# vcf20.net
KiCad netlist of a schematic drawn in EAGLE
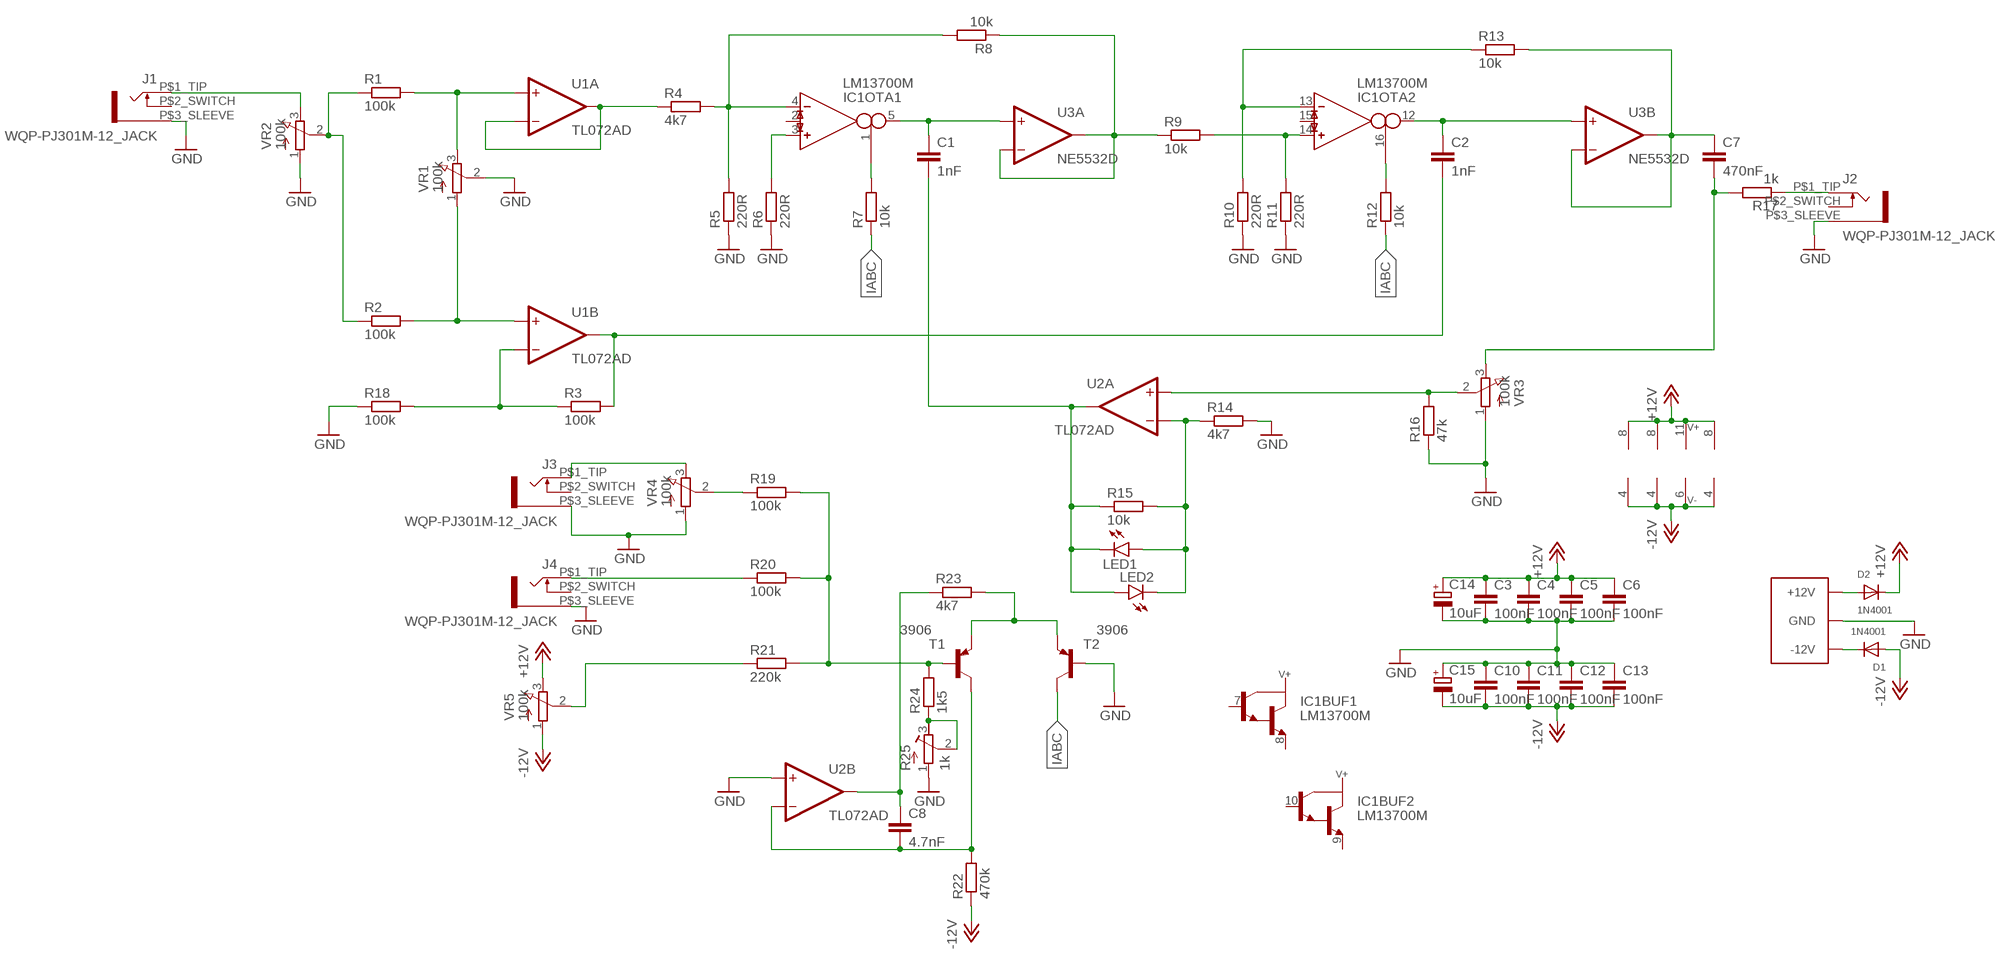
[diagram p0: schematic, sheet 1]

(export (version "E")
  (design (tool "Eeschema 10.0.6"))
  (components
    (comp (ref "C1")
      (value "1nF")
      (footprint "eagle-import:C0402")
      (libsource (lib "eagle-import") (part "C-EUC0402"))
    )
    (comp (ref "C2")
      (value "1nF")
      (footprint "eagle-import:C0402")
      (libsource (lib "eagle-import") (part "C-EUC0402"))
    )
    (comp (ref "C3")
      (value "100nF")
      (footprint "eagle-import:C0402")
      (libsource (lib "eagle-import") (part "C-EUC0402"))
    )
    (comp (ref "C4")
      (value "100nF")
      (footprint "eagle-import:C0402")
      (libsource (lib "eagle-import") (part "C-EUC0402"))
    )
    (comp (ref "C5")
      (value "100nF")
      (footprint "eagle-import:C0402")
      (libsource (lib "eagle-import") (part "C-EUC0402"))
    )
    (comp (ref "C6")
      (value "100nF")
      (footprint "eagle-import:C0402")
      (libsource (lib "eagle-import") (part "C-EUC0402"))
    )
    (comp (ref "C7")
      (value "470nF")
      (footprint "eagle-import:C0402")
      (libsource (lib "eagle-import") (part "C-EUC0402"))
    )
    (comp (ref "C8")
      (value "4.7nF")
      (footprint "eagle-import:C0402")
      (libsource (lib "eagle-import") (part "C-EUC0402"))
    )
    (comp (ref "C9")
      (value "EURO_POWER_LOCKFAT-LOCK")
      (footprint "eagle-import:EURO_PWR_HEADER_LOCK")
      (libsource (lib "eagle-import") (part "EURO_POWER_LOCKFAT-LOCK"))
    )
    (comp (ref "C10")
      (value "100nF")
      (footprint "eagle-import:C0402")
      (libsource (lib "eagle-import") (part "C-EUC0402"))
    )
    (comp (ref "C11")
      (value "100nF")
      (footprint "eagle-import:C0402")
      (libsource (lib "eagle-import") (part "C-EUC0402"))
    )
    (comp (ref "C12")
      (value "100nF")
      (footprint "eagle-import:C0402")
      (libsource (lib "eagle-import") (part "C-EUC0402"))
    )
    (comp (ref "C13")
      (value "100nF")
      (footprint "eagle-import:C0402")
      (libsource (lib "eagle-import") (part "C-EUC0402"))
    )
    (comp (ref "C14")
      (value "10uF")
      (footprint "eagle-import:PANASONIC_C")
      (libsource (lib "eagle-import") (part "CPOL-EUC"))
    )
    (comp (ref "C15")
      (value "10uF")
      (footprint "eagle-import:PANASONIC_C")
      (libsource (lib "eagle-import") (part "CPOL-EUC"))
    )
    (comp (ref "D1")
      (value "1N4001")
      (footprint "eagle-import:SMADIODE")
      (libsource (lib "eagle-import") (part "DIODESMA"))
    )
    (comp (ref "D2")
      (value "1N4001")
      (footprint "eagle-import:SMADIODE")
      (libsource (lib "eagle-import") (part "DIODESMA"))
    )
    (comp (ref "IC1")
      (value "LM13700M")
      (footprint "eagle-import:SO16")
      (libsource (lib "eagle-import") (part "LM13700M"))
    )
    (comp (ref "J1")
      (value "WQP-PJ301M-12_JACK")
      (footprint "eagle-import:WQP-PJ301M-12_JACK")
      (libsource (lib "eagle-import") (part "WQP-PJ301M-12_JACK"))
    )
    (comp (ref "J2")
      (value "WQP-PJ301M-12_JACK")
      (footprint "eagle-import:WQP-PJ301M-12_JACK")
      (libsource (lib "eagle-import") (part "WQP-PJ301M-12_JACK"))
    )
    (comp (ref "J3")
      (value "WQP-PJ301M-12_JACK")
      (footprint "eagle-import:WQP-PJ301M-12_JACK")
      (libsource (lib "eagle-import") (part "WQP-PJ301M-12_JACK"))
    )
    (comp (ref "J4")
      (value "WQP-PJ301M-12_JACK")
      (footprint "eagle-import:WQP-PJ301M-12_JACK")
      (libsource (lib "eagle-import") (part "WQP-PJ301M-12_JACK"))
    )
    (comp (ref "LED1")
      (value "LEDSML0603")
      (footprint "eagle-import:SML0603")
      (libsource (lib "eagle-import") (part "LEDSML0603"))
    )
    (comp (ref "LED2")
      (value "LEDSML0603")
      (footprint "eagle-import:SML0603")
      (libsource (lib "eagle-import") (part "LEDSML0603"))
    )
    (comp (ref "R1")
      (value "100k")
      (footprint "eagle-import:R0402")
      (libsource (lib "eagle-import") (part "R-EU_R0402"))
    )
    (comp (ref "R2")
      (value "100k")
      (footprint "eagle-import:R0402")
      (libsource (lib "eagle-import") (part "R-EU_R0402"))
    )
    (comp (ref "R3")
      (value "100k")
      (footprint "eagle-import:R0402")
      (libsource (lib "eagle-import") (part "R-EU_R0402"))
    )
    (comp (ref "R4")
      (value "4k7")
      (footprint "eagle-import:R0402")
      (libsource (lib "eagle-import") (part "R-EU_R0402"))
    )
    (comp (ref "R5")
      (value "220R")
      (footprint "eagle-import:R0402")
      (libsource (lib "eagle-import") (part "R-EU_R0402"))
    )
    (comp (ref "R6")
      (value "220R")
      (footprint "eagle-import:R0402")
      (libsource (lib "eagle-import") (part "R-EU_R0402"))
    )
    (comp (ref "R7")
      (value "10k")
      (footprint "eagle-import:R0402")
      (libsource (lib "eagle-import") (part "R-EU_R0402"))
    )
    (comp (ref "R8")
      (value "10k")
      (footprint "eagle-import:R0402")
      (libsource (lib "eagle-import") (part "R-EU_R0402"))
    )
    (comp (ref "R9")
      (value "10k")
      (footprint "eagle-import:R0402")
      (libsource (lib "eagle-import") (part "R-EU_R0402"))
    )
    (comp (ref "R10")
      (value "220R")
      (footprint "eagle-import:R0402")
      (libsource (lib "eagle-import") (part "R-EU_R0402"))
    )
    (comp (ref "R11")
      (value "220R")
      (footprint "eagle-import:R0402")
      (libsource (lib "eagle-import") (part "R-EU_R0402"))
    )
    (comp (ref "R12")
      (value "10k")
      (footprint "eagle-import:R0402")
      (libsource (lib "eagle-import") (part "R-EU_R0402"))
    )
    (comp (ref "R13")
      (value "10k")
      (footprint "eagle-import:R0402")
      (libsource (lib "eagle-import") (part "R-EU_R0402"))
    )
    (comp (ref "R14")
      (value "4k7")
      (footprint "eagle-import:R0402")
      (libsource (lib "eagle-import") (part "R-EU_R0402"))
    )
    (comp (ref "R15")
      (value "10k")
      (footprint "eagle-import:R0402")
      (libsource (lib "eagle-import") (part "R-EU_R0402"))
    )
    (comp (ref "R16")
      (value "47k")
      (footprint "eagle-import:R0402")
      (libsource (lib "eagle-import") (part "R-EU_R0402"))
    )
    (comp (ref "R17")
      (value "1k")
      (footprint "eagle-import:R0402")
      (libsource (lib "eagle-import") (part "R-EU_R0402"))
    )
    (comp (ref "R18")
      (value "100k")
      (footprint "eagle-import:R0402")
      (libsource (lib "eagle-import") (part "R-EU_R0402"))
    )
    (comp (ref "R19")
      (value "100k")
      (footprint "eagle-import:R0402")
      (libsource (lib "eagle-import") (part "R-EU_R0402"))
    )
    (comp (ref "R20")
      (value "100k")
      (footprint "eagle-import:R0402")
      (libsource (lib "eagle-import") (part "R-EU_R0402"))
    )
    (comp (ref "R21")
      (value "220k")
      (footprint "eagle-import:R0402")
      (libsource (lib "eagle-import") (part "R-EU_R0402"))
    )
    (comp (ref "R22")
      (value "470k")
      (footprint "eagle-import:R0402")
      (libsource (lib "eagle-import") (part "R-EU_R0402"))
    )
    (comp (ref "R23")
      (value "4k7")
      (footprint "eagle-import:R0402")
      (libsource (lib "eagle-import") (part "R-EU_R0402"))
    )
    (comp (ref "R24")
      (value "1k5")
      (footprint "eagle-import:R0402")
      (libsource (lib "eagle-import") (part "R-EU_R0402"))
    )
    (comp (ref "R25")
      (value "1k")
      (footprint "eagle-import:RTRIM64W")
      (libsource (lib "eagle-import") (part "R-TRIMM64W"))
    )
    (comp (ref "T1")
      (value "3906")
      (footprint "eagle-import:SOT23-BEC")
      (libsource (lib "eagle-import") (part "-PNP-SOT23-BECMMBT3906LT1"))
    )
    (comp (ref "T2")
      (value "3906")
      (footprint "eagle-import:SOT23-BEC")
      (libsource (lib "eagle-import") (part "-PNP-SOT23-BECMMBT3906LT1"))
    )
    (comp (ref "U1")
      (value "TL072AD")
      (footprint "eagle-import:SOIC8")
      (libsource (lib "eagle-import") (part "TL072DA"))
    )
    (comp (ref "U2")
      (value "TL072AD")
      (footprint "eagle-import:SOIC8")
      (libsource (lib "eagle-import") (part "TL072DA"))
    )
    (comp (ref "U3")
      (value "NE5532D")
      (footprint "eagle-import:SOIC8")
      (libsource (lib "eagle-import") (part "NE5532D"))
    )
    (comp (ref "VR1")
      (value "100k")
      (footprint "eagle-import:9MM_SNAP-IN_POT")
      (libsource (lib "eagle-import") (part "9MM_SNAP-IN_POT_"))
    )
    (comp (ref "VR2")
      (value "100k")
      (footprint "eagle-import:9MM_SNAP-IN_POT")
      (libsource (lib "eagle-import") (part "9MM_SNAP-IN_POT_"))
    )
    (comp (ref "VR3")
      (value "100k")
      (footprint "eagle-import:9MM_SNAP-IN_POT")
      (libsource (lib "eagle-import") (part "9MM_SNAP-IN_POT_"))
    )
    (comp (ref "VR4")
      (value "100k")
      (footprint "eagle-import:9MM_SNAP-IN_POT")
      (libsource (lib "eagle-import") (part "9MM_SNAP-IN_POT_"))
    )
    (comp (ref "VR5")
      (value "100k")
      (footprint "eagle-import:9MM_SNAP-IN_POT")
      (libsource (lib "eagle-import") (part "9MM_SNAP-IN_POT_"))
    )
  )
  (nets
    (net (code "1") (name "+12V") (class "Default")
      (node (ref "C14") (pin "+") (pinfunction "+_+") (pintype "passive"))
      (node (ref "C3") (pin "1") (pinfunction "1_1") (pintype "passive"))
      (node (ref "C4") (pin "1") (pinfunction "1_1") (pintype "passive"))
      (node (ref "C5") (pin "1") (pinfunction "1_1") (pintype "passive"))
      (node (ref "C6") (pin "1") (pinfunction "1_1") (pintype "passive"))
      (node (ref "D2") (pin "C") (pinfunction "C_C") (pintype "passive"))
      (node (ref "IC1") (pin "11") (pinfunction "V+_11") (pintype "power_in"))
      (node (ref "U1") (pin "8") (pinfunction "V+_8") (pintype "power_in"))
      (node (ref "U2") (pin "8") (pinfunction "V+_8") (pintype "power_in"))
      (node (ref "U3") (pin "8") (pinfunction "V+_8") (pintype "power_in"))
      (node (ref "VR5") (pin "3") (pinfunction "E_3") (pintype "passive"))
    )
    (net (code "2") (name "-12V") (class "Default")
      (node (ref "C10") (pin "2") (pinfunction "2_2") (pintype "passive"))
      (node (ref "C11") (pin "2") (pinfunction "2_2") (pintype "passive"))
      (node (ref "C12") (pin "2") (pinfunction "2_2") (pintype "passive"))
      (node (ref "C13") (pin "2") (pinfunction "2_2") (pintype "passive"))
      (node (ref "C15") (pin "-") (pinfunction "-_-") (pintype "passive"))
      (node (ref "D1") (pin "A") (pinfunction "A_A") (pintype "passive"))
      (node (ref "IC1") (pin "6") (pinfunction "V-_6") (pintype "power_in"))
      (node (ref "R22") (pin "1") (pinfunction "1_1") (pintype "passive"))
      (node (ref "U1") (pin "4") (pinfunction "V-_4") (pintype "power_in"))
      (node (ref "U2") (pin "4") (pinfunction "V-_4") (pintype "power_in"))
      (node (ref "U3") (pin "4") (pinfunction "V-_4") (pintype "power_in"))
      (node (ref "VR5") (pin "1") (pinfunction "A_1") (pintype "passive"))
    )
    (net (code "3") (name "GND") (class "Default")
      (node (ref "C10") (pin "1") (pinfunction "1_1") (pintype "passive"))
      (node (ref "C11") (pin "1") (pinfunction "1_1") (pintype "passive"))
      (node (ref "C12") (pin "1") (pinfunction "1_1") (pintype "passive"))
      (node (ref "C13") (pin "1") (pinfunction "1_1") (pintype "passive"))
      (node (ref "C14") (pin "-") (pinfunction "-_-") (pintype "passive"))
      (node (ref "C15") (pin "+") (pinfunction "+_+") (pintype "passive"))
      (node (ref "C3") (pin "2") (pinfunction "2_2") (pintype "passive"))
      (node (ref "C4") (pin "2") (pinfunction "2_2") (pintype "passive"))
      (node (ref "C5") (pin "2") (pinfunction "2_2") (pintype "passive"))
      (node (ref "C6") (pin "2") (pinfunction "2_2") (pintype "passive"))
      (node (ref "C9") (pin "GND1") (pinfunction "GND_GND1") (pintype "bidirectional"))
      (node (ref "C9") (pin "GND2") (pinfunction "GND_GND2") (pintype "bidirectional"))
      (node (ref "C9") (pin "GND3") (pinfunction "GND_GND3") (pintype "bidirectional"))
      (node (ref "C9") (pin "GND4") (pinfunction "GND_GND4") (pintype "bidirectional"))
      (node (ref "C9") (pin "GND5") (pinfunction "GND_GND5") (pintype "bidirectional"))
      (node (ref "C9") (pin "GND6") (pinfunction "GND_GND6") (pintype "bidirectional"))
      (node (ref "J1") (pin "P$3_SLEEVE") (pinfunction "1_P$3_SLEEVE") (pintype "passive"))
      (node (ref "J2") (pin "P$3_SLEEVE") (pinfunction "1_P$3_SLEEVE") (pintype "passive"))
      (node (ref "J3") (pin "P$3_SLEEVE") (pinfunction "1_P$3_SLEEVE") (pintype "passive"))
      (node (ref "J4") (pin "P$3_SLEEVE") (pinfunction "1_P$3_SLEEVE") (pintype "passive"))
      (node (ref "R10") (pin "1") (pinfunction "1_1") (pintype "passive"))
      (node (ref "R11") (pin "1") (pinfunction "1_1") (pintype "passive"))
      (node (ref "R14") (pin "2") (pinfunction "2_2") (pintype "passive"))
      (node (ref "R16") (pin "1") (pinfunction "1_1") (pintype "passive"))
      (node (ref "R18") (pin "1") (pinfunction "1_1") (pintype "passive"))
      (node (ref "R25") (pin "1") (pinfunction "A_1") (pintype "passive"))
      (node (ref "R5") (pin "1") (pinfunction "1_1") (pintype "passive"))
      (node (ref "R6") (pin "1") (pinfunction "1_1") (pintype "passive"))
      (node (ref "T2") (pin "B") (pinfunction "B_B") (pintype "passive"))
      (node (ref "U2") (pin "5") (pinfunction "+IN_5") (pintype "input"))
      (node (ref "VR1") (pin "2") (pinfunction "S_2") (pintype "passive"))
      (node (ref "VR2") (pin "1") (pinfunction "A_1") (pintype "passive"))
      (node (ref "VR3") (pin "1") (pinfunction "A_1") (pintype "passive"))
      (node (ref "VR4") (pin "1") (pinfunction "A_1") (pintype "passive"))
    )
    (net (code "4") (name "IABC") (class "Default")
      (node (ref "R12") (pin "1") (pinfunction "1_1") (pintype "passive"))
      (node (ref "R7") (pin "1") (pinfunction "1_1") (pintype "passive"))
      (node (ref "T2") (pin "C") (pinfunction "C_C") (pintype "passive"))
    )
    (net (code "5") (name "Net-(C9-+12V-PadPOS1)") (class "Default")
      (node (ref "C9") (pin "POS1") (pinfunction "+12V_POS1") (pintype "bidirectional"))
      (node (ref "C9") (pin "POS2") (pinfunction "+12V_POS2") (pintype "bidirectional"))
      (node (ref "D2") (pin "A") (pinfunction "A_A") (pintype "passive"))
    )
    (net (code "6") (name "Net-(C9--12V-PadNEG1)") (class "Default")
      (node (ref "C9") (pin "NEG1") (pinfunction "-12V_NEG1") (pintype "bidirectional"))
      (node (ref "C9") (pin "NEG2") (pinfunction "-12V_NEG2") (pintype "bidirectional"))
      (node (ref "D1") (pin "C") (pinfunction "C_C") (pintype "passive"))
    )
    (net (code "7") (name "Net-(IC1C-IN_N)") (class "Default")
      (node (ref "IC1") (pin "4") (pinfunction "IN_N_4") (pintype "input"))
      (node (ref "R4") (pin "2") (pinfunction "2_2") (pintype "passive"))
      (node (ref "R5") (pin "2") (pinfunction "2_2") (pintype "passive"))
      (node (ref "R8") (pin "2") (pinfunction "2_2") (pintype "passive"))
    )
    (net (code "8") (name "Net-(IC1C-IN_P)") (class "Default")
      (node (ref "IC1") (pin "3") (pinfunction "IN_P_3") (pintype "input"))
      (node (ref "R6") (pin "2") (pinfunction "2_2") (pintype "passive"))
    )
    (net (code "9") (name "Net-(IC1C-I_BIAS)") (class "Default")
      (node (ref "IC1") (pin "1") (pinfunction "I_BIAS_1") (pintype "input"))
      (node (ref "R7") (pin "2") (pinfunction "2_2") (pintype "passive"))
    )
    (net (code "10") (name "Net-(IC1C-OUT)") (class "Default")
      (node (ref "C1") (pin "1") (pinfunction "1_1") (pintype "passive"))
      (node (ref "IC1") (pin "5") (pinfunction "OUT_5") (pintype "output"))
      (node (ref "U3") (pin "3") (pinfunction "+IN_3") (pintype "input"))
    )
    (net (code "11") (name "Net-(IC1D-IN_N)") (class "Default")
      (node (ref "IC1") (pin "13") (pinfunction "IN_N_13") (pintype "input"))
      (node (ref "R10") (pin "2") (pinfunction "2_2") (pintype "passive"))
      (node (ref "R13") (pin "1") (pinfunction "1_1") (pintype "passive"))
    )
    (net (code "12") (name "Net-(IC1D-IN_P)") (class "Default")
      (node (ref "IC1") (pin "14") (pinfunction "IN_P_14") (pintype "input"))
      (node (ref "R11") (pin "2") (pinfunction "2_2") (pintype "passive"))
      (node (ref "R9") (pin "2") (pinfunction "2_2") (pintype "passive"))
    )
    (net (code "13") (name "Net-(IC1D-I_BIAS)") (class "Default")
      (node (ref "IC1") (pin "16") (pinfunction "I_BIAS_16") (pintype "input"))
      (node (ref "R12") (pin "2") (pinfunction "2_2") (pintype "passive"))
    )
    (net (code "14") (name "Net-(IC1D-OUT)") (class "Default")
      (node (ref "C2") (pin "1") (pinfunction "1_1") (pintype "passive"))
      (node (ref "IC1") (pin "12") (pinfunction "OUT_12") (pintype "output"))
      (node (ref "U3") (pin "5") (pinfunction "+IN_5") (pintype "input"))
    )
    (net (code "15") (name "Net-(J1-2)") (class "Default")
      (node (ref "J1") (pin "P$1_TIP") (pinfunction "2_P$1_TIP") (pintype "passive"))
      (node (ref "VR2") (pin "3") (pinfunction "E_3") (pintype "passive"))
    )
    (net (code "16") (name "Net-(J2-2)") (class "Default")
      (node (ref "J2") (pin "P$1_TIP") (pinfunction "2_P$1_TIP") (pintype "passive"))
      (node (ref "R17") (pin "1") (pinfunction "1_1") (pintype "passive"))
    )
    (net (code "17") (name "Net-(J3-2)") (class "Default")
      (node (ref "J3") (pin "P$1_TIP") (pinfunction "2_P$1_TIP") (pintype "passive"))
      (node (ref "VR4") (pin "3") (pinfunction "E_3") (pintype "passive"))
    )
    (net (code "18") (name "Net-(J4-2)") (class "Default")
      (node (ref "J4") (pin "P$1_TIP") (pinfunction "2_P$1_TIP") (pintype "passive"))
      (node (ref "R20") (pin "1") (pinfunction "1_1") (pintype "passive"))
    )
    (net (code "19") (name "Net-(R19-Pad2)") (class "Default")
      (node (ref "R19") (pin "2") (pinfunction "2_2") (pintype "passive"))
      (node (ref "R20") (pin "2") (pinfunction "2_2") (pintype "passive"))
      (node (ref "R21") (pin "2") (pinfunction "2_2") (pintype "passive"))
      (node (ref "R24") (pin "2") (pinfunction "2_2") (pintype "passive"))
      (node (ref "T1") (pin "B") (pinfunction "B_B") (pintype "passive"))
    )
    (net (code "20") (name "Net-(R23-Pad2)") (class "Default")
      (node (ref "R23") (pin "2") (pinfunction "2_2") (pintype "passive"))
      (node (ref "T1") (pin "E") (pinfunction "E_E") (pintype "passive"))
      (node (ref "T2") (pin "E") (pinfunction "E_E") (pintype "passive"))
    )
    (net (code "21") (name "Net-(R25-E)") (class "Default")
      (node (ref "R24") (pin "1") (pinfunction "1_1") (pintype "passive"))
      (node (ref "R25") (pin "2") (pinfunction "S_2") (pintype "passive"))
      (node (ref "R25") (pin "3") (pinfunction "E_3") (pintype "passive"))
    )
    (net (code "22") (name "Net-(U1A-+IN)") (class "Default")
      (node (ref "R1") (pin "2") (pinfunction "2_2") (pintype "passive"))
      (node (ref "U1") (pin "3") (pinfunction "+IN_3") (pintype "input"))
      (node (ref "VR1") (pin "3") (pinfunction "E_3") (pintype "passive"))
    )
    (net (code "23") (name "Net-(U1A--IN)") (class "Default")
      (node (ref "R4") (pin "1") (pinfunction "1_1") (pintype "passive"))
      (node (ref "U1") (pin "1") (pinfunction "OUT_1") (pintype "output"))
      (node (ref "U1") (pin "2") (pinfunction "-IN_2") (pintype "input"))
    )
    (net (code "24") (name "Net-(U1B-+IN)") (class "Default")
      (node (ref "R2") (pin "2") (pinfunction "2_2") (pintype "passive"))
      (node (ref "U1") (pin "5") (pinfunction "+IN_5") (pintype "input"))
      (node (ref "VR1") (pin "1") (pinfunction "A_1") (pintype "passive"))
    )
    (net (code "25") (name "Net-(U1B--IN)") (class "Default")
      (node (ref "R18") (pin "2") (pinfunction "2_2") (pintype "passive"))
      (node (ref "R3") (pin "1") (pinfunction "1_1") (pintype "passive"))
      (node (ref "U1") (pin "6") (pinfunction "-IN_6") (pintype "input"))
    )
    (net (code "26") (name "Net-(U1B-OUT)") (class "Default")
      (node (ref "C2") (pin "2") (pinfunction "2_2") (pintype "passive"))
      (node (ref "R3") (pin "2") (pinfunction "2_2") (pintype "passive"))
      (node (ref "U1") (pin "7") (pinfunction "OUT_7") (pintype "output"))
    )
    (net (code "27") (name "Net-(U2A-+IN)") (class "Default")
      (node (ref "R16") (pin "2") (pinfunction "2_2") (pintype "passive"))
      (node (ref "U2") (pin "3") (pinfunction "+IN_3") (pintype "input"))
      (node (ref "VR3") (pin "2") (pinfunction "S_2") (pintype "passive"))
    )
    (net (code "28") (name "Net-(U2A--IN)") (class "Default")
      (node (ref "LED1") (pin "A") (pinfunction "A_A") (pintype "passive"))
      (node (ref "LED2") (pin "C") (pinfunction "C_C") (pintype "passive"))
      (node (ref "R14") (pin "1") (pinfunction "1_1") (pintype "passive"))
      (node (ref "R15") (pin "2") (pinfunction "2_2") (pintype "passive"))
      (node (ref "U2") (pin "2") (pinfunction "-IN_2") (pintype "input"))
    )
    (net (code "29") (name "Net-(U2A-OUT)") (class "Default")
      (node (ref "C1") (pin "2") (pinfunction "2_2") (pintype "passive"))
      (node (ref "LED1") (pin "C") (pinfunction "C_C") (pintype "passive"))
      (node (ref "LED2") (pin "A") (pinfunction "A_A") (pintype "passive"))
      (node (ref "R15") (pin "1") (pinfunction "1_1") (pintype "passive"))
      (node (ref "U2") (pin "1") (pinfunction "OUT_1") (pintype "output"))
    )
    (net (code "30") (name "Net-(U2B--IN)") (class "Default")
      (node (ref "C8") (pin "2") (pinfunction "2_2") (pintype "passive"))
      (node (ref "R22") (pin "2") (pinfunction "2_2") (pintype "passive"))
      (node (ref "T1") (pin "C") (pinfunction "C_C") (pintype "passive"))
      (node (ref "U2") (pin "6") (pinfunction "-IN_6") (pintype "input"))
    )
    (net (code "31") (name "Net-(U2B-OUT)") (class "Default")
      (node (ref "C8") (pin "1") (pinfunction "1_1") (pintype "passive"))
      (node (ref "R23") (pin "1") (pinfunction "1_1") (pintype "passive"))
      (node (ref "U2") (pin "7") (pinfunction "OUT_7") (pintype "output"))
    )
    (net (code "32") (name "Net-(U3A--IN)") (class "Default")
      (node (ref "R8") (pin "1") (pinfunction "1_1") (pintype "passive"))
      (node (ref "R9") (pin "1") (pinfunction "1_1") (pintype "passive"))
      (node (ref "U3") (pin "1") (pinfunction "OUT_1") (pintype "output"))
      (node (ref "U3") (pin "2") (pinfunction "-IN_2") (pintype "input"))
    )
    (net (code "33") (name "Net-(U3B--IN)") (class "Default")
      (node (ref "C7") (pin "1") (pinfunction "1_1") (pintype "passive"))
      (node (ref "R13") (pin "2") (pinfunction "2_2") (pintype "passive"))
      (node (ref "U3") (pin "6") (pinfunction "-IN_6") (pintype "input"))
      (node (ref "U3") (pin "7") (pinfunction "OUT_7") (pintype "output"))
    )
    (net (code "34") (name "Net-(VR2-S)") (class "Default")
      (node (ref "R1") (pin "1") (pinfunction "1_1") (pintype "passive"))
      (node (ref "R2") (pin "1") (pinfunction "1_1") (pintype "passive"))
      (node (ref "VR2") (pin "2") (pinfunction "S_2") (pintype "passive"))
    )
    (net (code "35") (name "Net-(VR3-E)") (class "Default")
      (node (ref "C7") (pin "2") (pinfunction "2_2") (pintype "passive"))
      (node (ref "R17") (pin "2") (pinfunction "2_2") (pintype "passive"))
      (node (ref "VR3") (pin "3") (pinfunction "E_3") (pintype "passive"))
    )
    (net (code "36") (name "Net-(VR4-S)") (class "Default")
      (node (ref "R19") (pin "1") (pinfunction "1_1") (pintype "passive"))
      (node (ref "VR4") (pin "2") (pinfunction "S_2") (pintype "passive"))
    )
    (net (code "37") (name "Net-(VR5-S)") (class "Default")
      (node (ref "R21") (pin "1") (pinfunction "1_1") (pintype "passive"))
      (node (ref "VR5") (pin "2") (pinfunction "S_2") (pintype "passive"))
    )
    (net (code "38") (name "unconnected-(IC1A-B-Pad7)") (class "Default")
      (node (ref "IC1") (pin "7") (pinfunction "B_7") (pintype "passive"))
    )
    (net (code "39") (name "unconnected-(IC1A-E-Pad8)") (class "Default")
      (node (ref "IC1") (pin "8") (pinfunction "E_8") (pintype "passive"))
    )
    (net (code "40") (name "unconnected-(IC1B-B-Pad10)") (class "Default")
      (node (ref "IC1") (pin "10") (pinfunction "B_10") (pintype "passive"))
    )
    (net (code "41") (name "unconnected-(IC1B-E-Pad9)") (class "Default")
      (node (ref "IC1") (pin "9") (pinfunction "E_9") (pintype "passive"))
    )
    (net (code "42") (name "unconnected-(IC1C-I_DIODE-Pad2)") (class "Default")
      (node (ref "IC1") (pin "2") (pinfunction "I_DIODE_2") (pintype "input"))
    )
    (net (code "43") (name "unconnected-(IC1D-I_DIODE-Pad15)") (class "Default")
      (node (ref "IC1") (pin "15") (pinfunction "I_DIODE_15") (pintype "input"))
    )
    (net (code "44") (name "unconnected-(J1-3-PadP$2_SWITCH)") (class "Default")
      (node (ref "J1") (pin "P$2_SWITCH") (pinfunction "3_P$2_SWITCH") (pintype "passive"))
    )
    (net (code "45") (name "unconnected-(J2-3-PadP$2_SWITCH)") (class "Default")
      (node (ref "J2") (pin "P$2_SWITCH") (pinfunction "3_P$2_SWITCH") (pintype "passive"))
    )
    (net (code "46") (name "unconnected-(J3-3-PadP$2_SWITCH)") (class "Default")
      (node (ref "J3") (pin "P$2_SWITCH") (pinfunction "3_P$2_SWITCH") (pintype "passive"))
    )
    (net (code "47") (name "unconnected-(J4-3-PadP$2_SWITCH)") (class "Default")
      (node (ref "J4") (pin "P$2_SWITCH") (pinfunction "3_P$2_SWITCH") (pintype "passive"))
    )
  )
)
